# SmartDriveTestStand.net
KiCad netlist of a schematic drawn in EAGLE
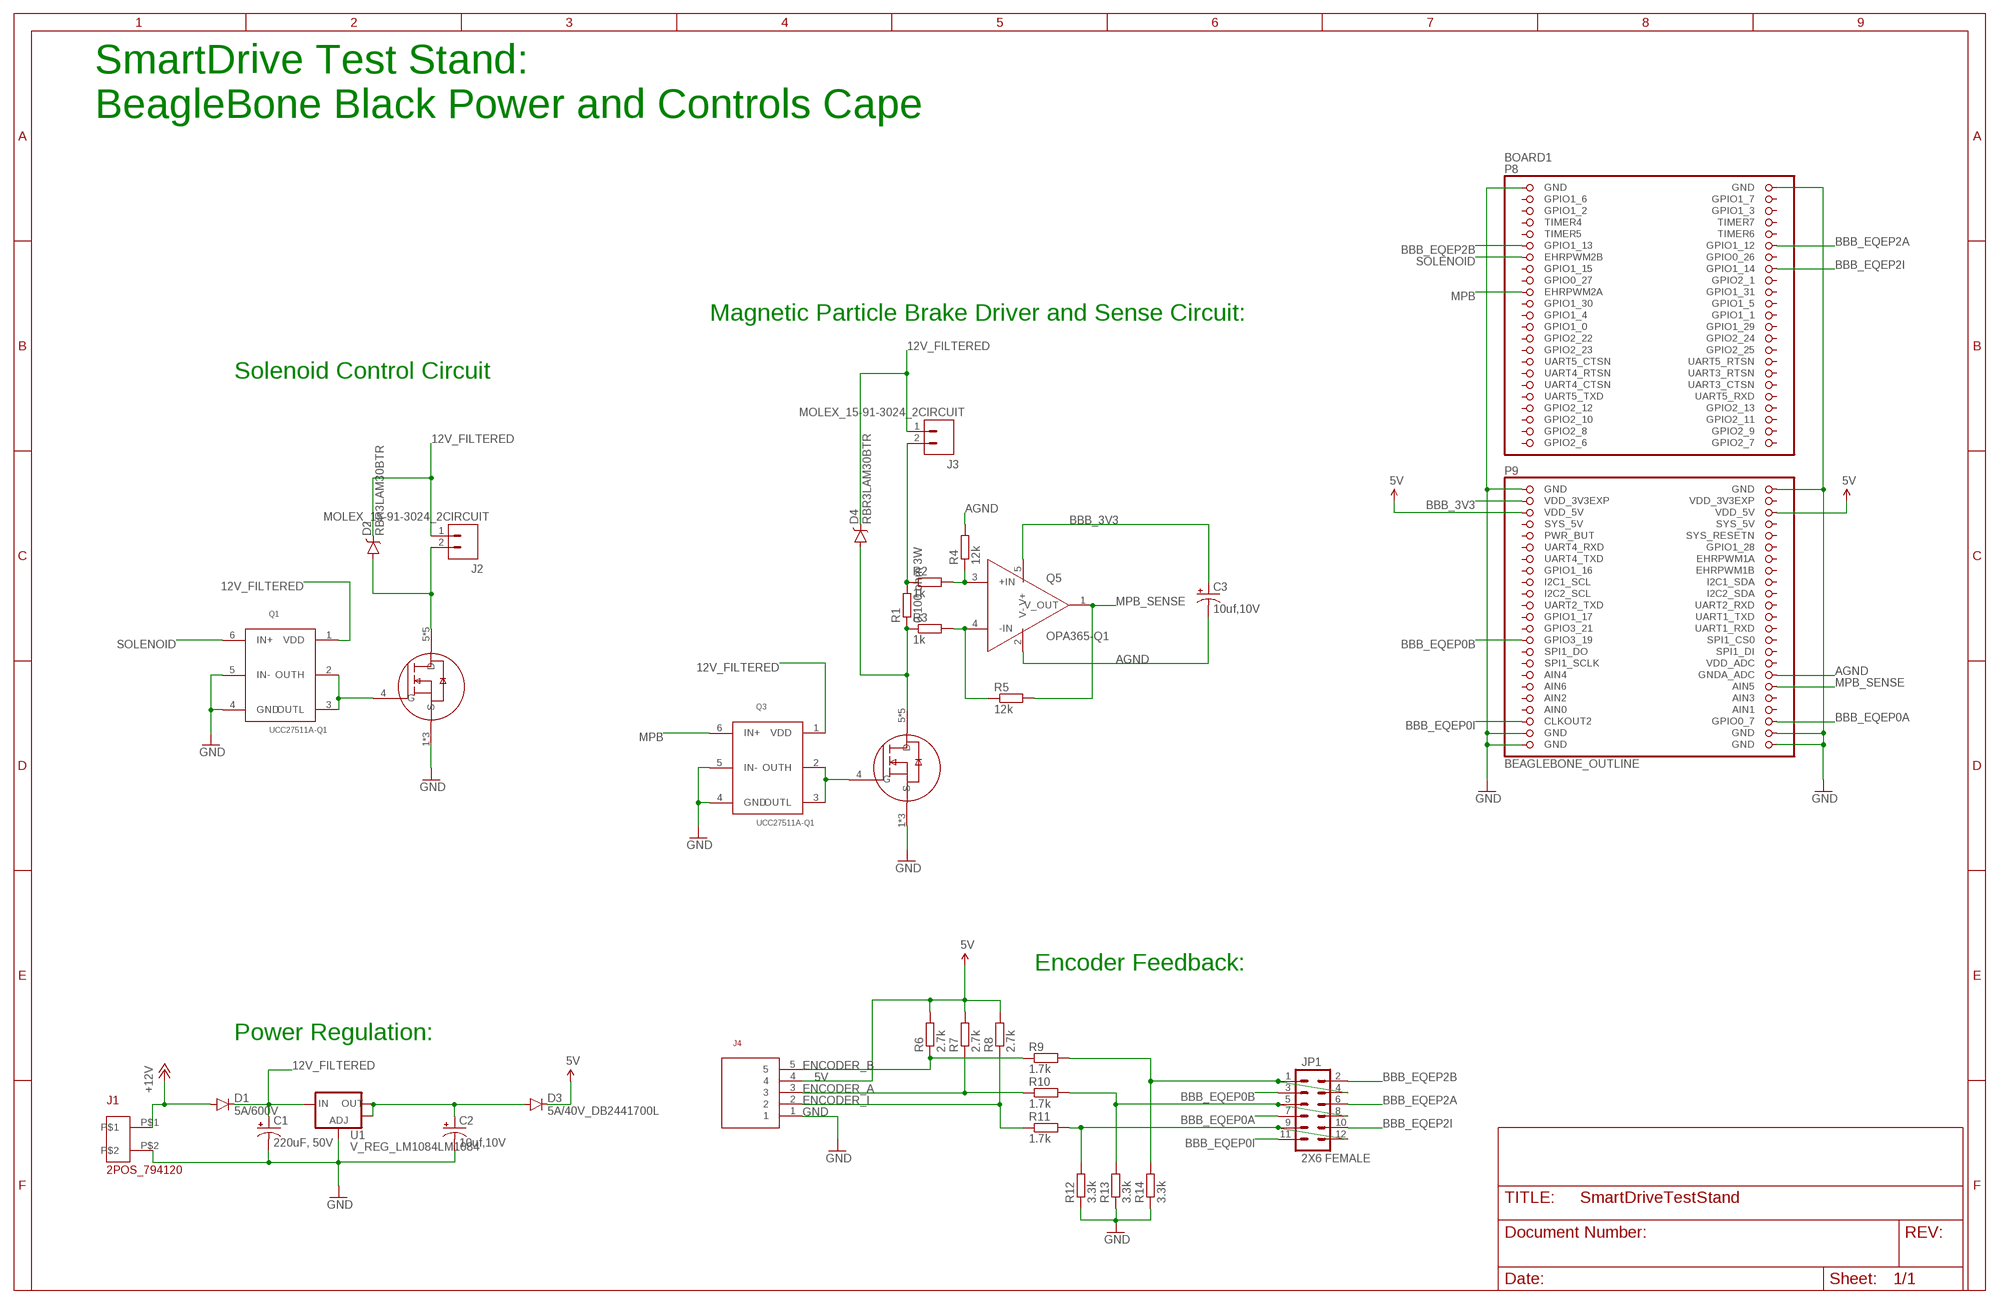
[diagram p0: schematic, sheet 1]

(export (version "E")
  (design (tool "Eeschema 10.0.6"))
  (components
    (comp (ref "BOARD1")
      (value "BEAGLEBONE_OUTLINE")
      (footprint "eagle-import:BEAGLEBONE_SHIELD")
      (libsource (lib "eagle-import") (part "BEAGLEBONE_OUTLINE"))
    )
    (comp (ref "C1")
      (value "220uF, 50V")
      (footprint "eagle-import:PANASONIC_G")
      (libsource (lib "eagle-import") (part "CAP_POLG"))
    )
    (comp (ref "C2")
      (value "10uf,10V")
      (footprint "eagle-import:EIA3216")
      (libsource (lib "eagle-import") (part "SparkFun-Passives_CAP_POL1206"))
    )
    (comp (ref "C3")
      (value "10uf,10V")
      (footprint "eagle-import:EIA3216")
      (libsource (lib "eagle-import") (part "SparkFun-Passives_CAP_POL1206"))
    )
    (comp (ref "D1")
      (value "5A/600V")
      (footprint "eagle-import:SMC")
      (libsource (lib "eagle-import") (part "DIODEES3J"))
    )
    (comp (ref "D2")
      (value "RBR3LAM30BTR")
      (footprint "eagle-import:SMA-DIODE")
      (libsource (lib "eagle-import") (part "DIODE-SCHOTTKYRBR3LAM30B"))
    )
    (comp (ref "D3")
      (value "5A/40V_DB2441700L")
      (footprint "eagle-import:SMA-DIODE_ALT")
      (libsource (lib "eagle-import") (part "DIODESMA-ALT"))
    )
    (comp (ref "D4")
      (value "RBR3LAM30BTR")
      (footprint "eagle-import:SMA-DIODE")
      (libsource (lib "eagle-import") (part "DIODE-SCHOTTKYRBR3LAM30B"))
    )
    (comp (ref "J1")
      (value "2POS_794120")
      (footprint "eagle-import:2POS_794120-1")
      (libsource (lib "eagle-import") (part "2POS_794120"))
    )
    (comp (ref "J2")
      (value "MOLEX_15-91-3024_2CIRCUIT")
      (footprint "eagle-import:MOLEX15-91-3024_2CIRCUIT")
      (libsource (lib "eagle-import") (part "MOLEX_15-91-3024_2CIRCUIT"))
    )
    (comp (ref "J3")
      (value "MOLEX_15-91-3024_2CIRCUIT")
      (footprint "eagle-import:MOLEX15-91-3024_2CIRCUIT")
      (libsource (lib "eagle-import") (part "MOLEX_15-91-3024_2CIRCUIT"))
    )
    (comp (ref "J4")
      (value "MOLEX_15-91-3053_5CIRCUIT")
      (footprint "eagle-import:MOLEX15-91-3053-5CIRCUIT")
      (libsource (lib "eagle-import") (part "MOLEX_15-91-3053_5CIRCUIT"))
    )
    (comp (ref "JP1")
      (value "2X6 FEMALE")
      (footprint "eagle-import:2X6")
      (libsource (lib "eagle-import") (part "M06X2PTH_FEMALE"))
    )
    (comp (ref "Q1")
      (value "UCC27511A-Q1")
      (footprint "eagle-import:SOT23-6")
      (libsource (lib "eagle-import") (part "UCC27511A-Q1"))
    )
    (comp (ref "Q2")
      (value "MOSFET_NCHANNELTI_CSD18533Q5A")
      (footprint "eagle-import:SON_5X6MM_NEXFET")
      (libsource (lib "eagle-import") (part "MOSFET_NCHANNELTI_CSD18533Q5A"))
    )
    (comp (ref "Q3")
      (value "UCC27511A-Q1")
      (footprint "eagle-import:SOT23-6")
      (libsource (lib "eagle-import") (part "UCC27511A-Q1"))
    )
    (comp (ref "Q4")
      (value "MOSFET_NCHANNELTI_CSD18533Q5A")
      (footprint "eagle-import:SON_5X6MM_NEXFET")
      (libsource (lib "eagle-import") (part "MOSFET_NCHANNELTI_CSD18533Q5A"))
    )
    (comp (ref "Q5")
      (value "OPA365-Q1")
      (footprint "eagle-import:SOT23-5")
      (libsource (lib "eagle-import") (part "OPA365-Q1"))
    )
    (comp (ref "R1")
      (value "0.100 ohm 3W")
      (footprint "eagle-import:RESISTOR-2512")
      (libsource (lib "eagle-import") (part "RESISTOR-2512"))
    )
    (comp (ref "R2")
      (value "1k")
      (footprint "eagle-import:RESISTOR-0603")
      (libsource (lib "eagle-import") (part "RESISTOR-0603"))
    )
    (comp (ref "R3")
      (value "1k")
      (footprint "eagle-import:RESISTOR-0603")
      (libsource (lib "eagle-import") (part "RESISTOR-0603"))
    )
    (comp (ref "R4")
      (value "12k")
      (footprint "eagle-import:RESISTOR-0603")
      (libsource (lib "eagle-import") (part "RESISTOR-0603"))
    )
    (comp (ref "R5")
      (value "12k")
      (footprint "eagle-import:RESISTOR-0603")
      (libsource (lib "eagle-import") (part "RESISTOR-0603"))
    )
    (comp (ref "R6")
      (value "2.7k")
      (footprint "eagle-import:RESISTOR-0603")
      (libsource (lib "eagle-import") (part "RESISTOR-0603"))
    )
    (comp (ref "R7")
      (value "2.7k")
      (footprint "eagle-import:RESISTOR-0603")
      (libsource (lib "eagle-import") (part "RESISTOR-0603"))
    )
    (comp (ref "R8")
      (value "2.7k")
      (footprint "eagle-import:RESISTOR-0603")
      (libsource (lib "eagle-import") (part "RESISTOR-0603"))
    )
    (comp (ref "R9")
      (value "1.7k")
      (footprint "eagle-import:RESISTOR-0603")
      (libsource (lib "eagle-import") (part "RESISTOR-0603"))
    )
    (comp (ref "R10")
      (value "1.7k")
      (footprint "eagle-import:RESISTOR-0603")
      (libsource (lib "eagle-import") (part "RESISTOR-0603"))
    )
    (comp (ref "R11")
      (value "1.7k")
      (footprint "eagle-import:RESISTOR-0603")
      (libsource (lib "eagle-import") (part "RESISTOR-0603"))
    )
    (comp (ref "R12")
      (value "3.3k")
      (footprint "eagle-import:RESISTOR-0603")
      (libsource (lib "eagle-import") (part "RESISTOR-0603"))
    )
    (comp (ref "R13")
      (value "3.3k")
      (footprint "eagle-import:RESISTOR-0603")
      (libsource (lib "eagle-import") (part "RESISTOR-0603"))
    )
    (comp (ref "R14")
      (value "3.3k")
      (footprint "eagle-import:RESISTOR-0603")
      (libsource (lib "eagle-import") (part "RESISTOR-0603"))
    )
    (comp (ref "U1")
      (value "V_REG_LM1084LM1084")
      (footprint "eagle-import:TO-263-3")
      (libsource (lib "eagle-import") (part "V_REG_LM1084LM1084"))
    )
  )
  (nets
    (net (code "1") (name "+12V") (class "Default")
      (node (ref "D1") (pin "A") (pinfunction "A_A") (pintype "passive"))
      (node (ref "J1") (pin "P$1") (pinfunction "P$1_P$1") (pintype "bidirectional"))
    )
    (net (code "2") (name "/12V_FILTERED") (class "Default")
      (node (ref "C1") (pin "+") (pinfunction "+_+") (pintype "passive"))
      (node (ref "D1") (pin "C") (pinfunction "C_C") (pintype "passive"))
      (node (ref "D2") (pin "C") (pinfunction "C_C") (pintype "passive"))
      (node (ref "D4") (pin "C") (pinfunction "C_C") (pintype "passive"))
      (node (ref "J2") (pin "1") (pinfunction "1_1") (pintype "passive"))
      (node (ref "J3") (pin "1") (pinfunction "1_1") (pintype "passive"))
      (node (ref "Q1") (pin "1") (pinfunction "VDD_1") (pintype "bidirectional"))
      (node (ref "Q3") (pin "1") (pinfunction "VDD_1") (pintype "bidirectional"))
      (node (ref "U1") (pin "3") (pinfunction "IN_3") (pintype "input"))
    )
    (net (code "3") (name "/AGND") (class "Default")
      (node (ref "BOARD1") (pin "80") (pinfunction "GNDA_ADC_80") (pintype "passive"))
      (node (ref "C3") (pin "C") (pinfunction "-_C") (pintype "passive"))
      (node (ref "Q5") (pin "2") (pinfunction "V-_2") (pintype "power_in"))
      (node (ref "R4") (pin "P$2") (pinfunction "2_P$2") (pintype "passive"))
    )
    (net (code "4") (name "/AIN0") (class "Default")
      (node (ref "BOARD1") (pin "85") (pinfunction "AIN0_85") (pintype "power_in"))
    )
    (net (code "5") (name "/BBB_3V3") (class "Default")
      (node (ref "BOARD1") (pin "49") (pinfunction "VDD_3V3EXP_49") (pintype "power_in"))
      (node (ref "C3") (pin "A") (pinfunction "+_A") (pintype "passive"))
      (node (ref "Q5") (pin "5") (pinfunction "V+_5") (pintype "power_in"))
    )
    (net (code "6") (name "/BBB_EQEP0A") (class "Default")
      (node (ref "BOARD1") (pin "88") (pinfunction "GPIO0_7_88") (pintype "passive"))
      (node (ref "JP1") (pin "7") (pinfunction "7_7") (pintype "passive"))
    )
    (net (code "7") (name "/BBB_EQEP0B") (class "Default")
      (node (ref "BOARD1") (pin "73") (pinfunction "GPIO3_19_73") (pintype "passive"))
      (node (ref "JP1") (pin "3") (pinfunction "3_3") (pintype "passive"))
    )
    (net (code "8") (name "/BBB_EQEP0I") (class "Default")
      (node (ref "BOARD1") (pin "87") (pinfunction "CLKOUT2_87") (pintype "input"))
      (node (ref "JP1") (pin "11") (pinfunction "11_11") (pintype "passive"))
    )
    (net (code "9") (name "/BBB_EQEP2A") (class "Default")
      (node (ref "BOARD1") (pin "12") (pinfunction "GPIO1_12_12") (pintype "passive"))
      (node (ref "JP1") (pin "6") (pinfunction "6_6") (pintype "passive"))
    )
    (net (code "10") (name "/BBB_EQEP2B") (class "Default")
      (node (ref "BOARD1") (pin "11") (pinfunction "GPIO1_13_11") (pintype "passive"))
      (node (ref "JP1") (pin "2") (pinfunction "2_2") (pintype "passive"))
    )
    (net (code "11") (name "/BBB_EQEP2I") (class "Default")
      (node (ref "BOARD1") (pin "16") (pinfunction "GPIO1_14_16") (pintype "passive"))
      (node (ref "JP1") (pin "10") (pinfunction "10_10") (pintype "passive"))
    )
    (net (code "12") (name "/ENCODER_A") (class "Default")
      (node (ref "J4") (pin "3") (pinfunction "3_3") (pintype "passive"))
      (node (ref "R10") (pin "P$1") (pinfunction "1_P$1") (pintype "passive"))
      (node (ref "R7") (pin "P$1") (pinfunction "1_P$1") (pintype "passive"))
    )
    (net (code "13") (name "/ENCODER_B") (class "Default")
      (node (ref "J4") (pin "5") (pinfunction "5_5") (pintype "passive"))
      (node (ref "R6") (pin "P$1") (pinfunction "1_P$1") (pintype "passive"))
      (node (ref "R9") (pin "P$1") (pinfunction "1_P$1") (pintype "passive"))
    )
    (net (code "14") (name "/ENCODER_I") (class "Default")
      (node (ref "J4") (pin "2") (pinfunction "2_2") (pintype "passive"))
      (node (ref "R11") (pin "P$1") (pinfunction "1_P$1") (pintype "passive"))
      (node (ref "R8") (pin "P$1") (pinfunction "1_P$1") (pintype "passive"))
    )
    (net (code "15") (name "/MPB") (class "Default")
      (node (ref "BOARD1") (pin "19") (pinfunction "EHRPWM2A_19") (pintype "passive"))
      (node (ref "Q3") (pin "6") (pinfunction "IN+_6") (pintype "bidirectional"))
    )
    (net (code "16") (name "/MPB_SENSE") (class "Default")
      (node (ref "BOARD1") (pin "82") (pinfunction "AIN5_82") (pintype "passive"))
      (node (ref "Q5") (pin "1") (pinfunction "V_OUT_1") (pintype "output"))
      (node (ref "R5") (pin "P$2") (pinfunction "2_P$2") (pintype "passive"))
    )
    (net (code "17") (name "/SOLENOID") (class "Default")
      (node (ref "BOARD1") (pin "13") (pinfunction "EHRPWM2B_13") (pintype "passive"))
      (node (ref "Q1") (pin "6") (pinfunction "IN+_6") (pintype "bidirectional"))
    )
    (net (code "18") (name "/SYS_5V") (class "Default")
      (node (ref "BOARD1") (pin "53") (pinfunction "SYS_5V_53") (pintype "power_in"))
    )
    (net (code "19") (name "/VDD_3V3EXP") (class "Default")
      (node (ref "BOARD1") (pin "50") (pinfunction "VDD_3V3EXP_50") (pintype "power_in"))
    )
    (net (code "20") (name "5V") (class "Default")
      (node (ref "BOARD1") (pin "51") (pinfunction "VDD_5V_51") (pintype "power_in"))
      (node (ref "BOARD1") (pin "52") (pinfunction "VDD_5V_52") (pintype "power_in"))
      (node (ref "D3") (pin "C") (pinfunction "C_C") (pintype "passive"))
      (node (ref "J4") (pin "4") (pinfunction "4_4") (pintype "passive"))
      (node (ref "R6") (pin "P$2") (pinfunction "2_P$2") (pintype "passive"))
      (node (ref "R7") (pin "P$2") (pinfunction "2_P$2") (pintype "passive"))
      (node (ref "R8") (pin "P$2") (pinfunction "2_P$2") (pintype "passive"))
    )
    (net (code "21") (name "GND") (class "Default")
      (node (ref "BOARD1") (pin "1") (pinfunction "GND_1") (pintype "power_in"))
      (node (ref "BOARD1") (pin "2") (pinfunction "GND_2") (pintype "power_in"))
      (node (ref "BOARD1") (pin "47") (pinfunction "GND_47") (pintype "power_in"))
      (node (ref "BOARD1") (pin "48") (pinfunction "GND_48") (pintype "power_in"))
      (node (ref "BOARD1") (pin "89") (pinfunction "GND_89") (pintype "power_in"))
      (node (ref "BOARD1") (pin "90") (pinfunction "GND_90") (pintype "power_in"))
      (node (ref "BOARD1") (pin "91") (pinfunction "GND_91") (pintype "power_in"))
      (node (ref "BOARD1") (pin "92") (pinfunction "GND_92") (pintype "power_in"))
      (node (ref "C1") (pin "-") (pinfunction "-_-") (pintype "passive"))
      (node (ref "C2") (pin "C") (pinfunction "-_C") (pintype "passive"))
      (node (ref "J1") (pin "P$2") (pinfunction "P$2_P$2") (pintype "bidirectional"))
      (node (ref "J4") (pin "1") (pinfunction "1_1") (pintype "passive"))
      (node (ref "Q1") (pin "4") (pinfunction "GND_4") (pintype "bidirectional"))
      (node (ref "Q1") (pin "5") (pinfunction "IN-_5") (pintype "bidirectional"))
      (node (ref "Q2") (pin "1") (pinfunction "S_1") (pintype "power_in"))
      (node (ref "Q2") (pin "2") (pinfunction "S_2") (pintype "power_in"))
      (node (ref "Q2") (pin "3") (pinfunction "S_3") (pintype "power_in"))
      (node (ref "Q3") (pin "4") (pinfunction "GND_4") (pintype "bidirectional"))
      (node (ref "Q3") (pin "5") (pinfunction "IN-_5") (pintype "bidirectional"))
      (node (ref "Q4") (pin "1") (pinfunction "S_1") (pintype "power_in"))
      (node (ref "Q4") (pin "2") (pinfunction "S_2") (pintype "power_in"))
      (node (ref "Q4") (pin "3") (pinfunction "S_3") (pintype "power_in"))
      (node (ref "R12") (pin "P$1") (pinfunction "1_P$1") (pintype "passive"))
      (node (ref "R13") (pin "P$1") (pinfunction "1_P$1") (pintype "passive"))
      (node (ref "R14") (pin "P$1") (pinfunction "1_P$1") (pintype "passive"))
      (node (ref "U1") (pin "1") (pinfunction "ADJ_1") (pintype "input"))
    )
    (net (code "22") (name "Net-(C2-+)") (class "Default")
      (node (ref "C2") (pin "A") (pinfunction "+_A") (pintype "passive"))
      (node (ref "D3") (pin "A") (pinfunction "A_A") (pintype "passive"))
      (node (ref "U1") (pin "2") (pinfunction "OUT_2") (pintype "output"))
      (node (ref "U1") (pin "4") (pinfunction "OUT_4") (pintype "output"))
    )
    (net (code "23") (name "Net-(D2-PadA)") (class "Default")
      (node (ref "D2") (pin "A") (pinfunction "A_A") (pintype "passive"))
      (node (ref "J2") (pin "2") (pinfunction "2_2") (pintype "passive"))
      (node (ref "Q2") (pin "5") (pinfunction "D_5") (pintype "power_in"))
      (node (ref "Q2") (pin "6") (pinfunction "D_6") (pintype "power_in"))
      (node (ref "Q2") (pin "7") (pinfunction "D_7") (pintype "power_in"))
      (node (ref "Q2") (pin "8") (pinfunction "D_8") (pintype "power_in"))
      (node (ref "Q2") (pin "PAD") (pinfunction "D_PAD") (pintype "power_in"))
    )
    (net (code "24") (name "Net-(Q1-OUTH)") (class "Default")
      (node (ref "Q1") (pin "2") (pinfunction "OUTH_2") (pintype "bidirectional"))
      (node (ref "Q1") (pin "3") (pinfunction "OUTL_3") (pintype "bidirectional"))
      (node (ref "Q2") (pin "4") (pinfunction "G_4") (pintype "input"))
    )
    (net (code "25") (name "Net-(Q3-OUTH)") (class "Default")
      (node (ref "Q3") (pin "2") (pinfunction "OUTH_2") (pintype "bidirectional"))
      (node (ref "Q3") (pin "3") (pinfunction "OUTL_3") (pintype "bidirectional"))
      (node (ref "Q4") (pin "4") (pinfunction "G_4") (pintype "input"))
    )
    (net (code "26") (name "Net-(Q5-+IN)") (class "Default")
      (node (ref "Q5") (pin "3") (pinfunction "+IN_3") (pintype "input"))
      (node (ref "R2") (pin "P$2") (pinfunction "2_P$2") (pintype "passive"))
      (node (ref "R4") (pin "P$1") (pinfunction "1_P$1") (pintype "passive"))
    )
    (net (code "27") (name "Net-(Q5--IN)") (class "Default")
      (node (ref "Q5") (pin "4") (pinfunction "-IN_4") (pintype "input"))
      (node (ref "R3") (pin "P$2") (pinfunction "2_P$2") (pintype "passive"))
      (node (ref "R5") (pin "P$1") (pinfunction "1_P$1") (pintype "passive"))
    )
    (net (code "28") (name "Net-(R2-1)") (class "Default")
      (node (ref "J3") (pin "2") (pinfunction "2_2") (pintype "passive"))
      (node (ref "R1") (pin "2") (pinfunction "2_2") (pintype "passive"))
      (node (ref "R2") (pin "P$1") (pinfunction "1_P$1") (pintype "passive"))
    )
    (net (code "29") (name "Net-(R3-1)") (class "Default")
      (node (ref "D4") (pin "A") (pinfunction "A_A") (pintype "passive"))
      (node (ref "Q4") (pin "5") (pinfunction "D_5") (pintype "power_in"))
      (node (ref "Q4") (pin "6") (pinfunction "D_6") (pintype "power_in"))
      (node (ref "Q4") (pin "7") (pinfunction "D_7") (pintype "power_in"))
      (node (ref "Q4") (pin "8") (pinfunction "D_8") (pintype "power_in"))
      (node (ref "Q4") (pin "PAD") (pinfunction "D_PAD") (pintype "power_in"))
      (node (ref "R1") (pin "1") (pinfunction "1_1") (pintype "passive"))
      (node (ref "R3") (pin "P$1") (pinfunction "1_P$1") (pintype "passive"))
    )
    (net (code "30") (name "Net-(R10-2)") (class "Default")
      (node (ref "JP1") (pin "5") (pinfunction "5_5") (pintype "passive"))
      (node (ref "JP1") (pin "8") (pinfunction "8_8") (pintype "passive"))
      (node (ref "R10") (pin "P$2") (pinfunction "2_P$2") (pintype "passive"))
      (node (ref "R13") (pin "P$2") (pinfunction "2_P$2") (pintype "passive"))
    )
    (net (code "31") (name "Net-(R11-2)") (class "Default")
      (node (ref "JP1") (pin "12") (pinfunction "12_12") (pintype "passive"))
      (node (ref "JP1") (pin "9") (pinfunction "9_9") (pintype "passive"))
      (node (ref "R11") (pin "P$2") (pinfunction "2_P$2") (pintype "passive"))
      (node (ref "R12") (pin "P$2") (pinfunction "2_P$2") (pintype "passive"))
    )
    (net (code "32") (name "Net-(R14-2)") (class "Default")
      (node (ref "JP1") (pin "1") (pinfunction "1_1") (pintype "passive"))
      (node (ref "JP1") (pin "4") (pinfunction "4_4") (pintype "passive"))
      (node (ref "R14") (pin "P$2") (pinfunction "2_P$2") (pintype "passive"))
      (node (ref "R9") (pin "P$2") (pinfunction "2_P$2") (pintype "passive"))
    )
    (net (code "33") (name "unconnected-(BOARD1-AIN1-Pad86)") (class "Default")
      (node (ref "BOARD1") (pin "86") (pinfunction "AIN1_86") (pintype "passive"))
    )
    (net (code "34") (name "unconnected-(BOARD1-AIN2-Pad83)") (class "Default")
      (node (ref "BOARD1") (pin "83") (pinfunction "AIN2_83") (pintype "passive"))
    )
    (net (code "35") (name "unconnected-(BOARD1-AIN3-Pad84)") (class "Default")
      (node (ref "BOARD1") (pin "84") (pinfunction "AIN3_84") (pintype "passive"))
    )
    (net (code "36") (name "unconnected-(BOARD1-AIN4-Pad79)") (class "Default")
      (node (ref "BOARD1") (pin "79") (pinfunction "AIN4_79") (pintype "passive"))
    )
    (net (code "37") (name "unconnected-(BOARD1-AIN6-Pad81)") (class "Default")
      (node (ref "BOARD1") (pin "81") (pinfunction "AIN6_81") (pintype "passive"))
    )
    (net (code "38") (name "unconnected-(BOARD1-EHRPWM1A-Pad60)") (class "Default")
      (node (ref "BOARD1") (pin "60") (pinfunction "EHRPWM1A_60") (pintype "passive"))
    )
    (net (code "39") (name "unconnected-(BOARD1-EHRPWM1B-Pad62)") (class "Default")
      (node (ref "BOARD1") (pin "62") (pinfunction "EHRPWM1B_62") (pintype "passive"))
    )
    (net (code "40") (name "unconnected-(BOARD1-GPIO0_26-Pad14)") (class "Default")
      (node (ref "BOARD1") (pin "14") (pinfunction "GPIO0_26_14") (pintype "passive"))
    )
    (net (code "41") (name "unconnected-(BOARD1-GPIO0_27-Pad17)") (class "Default")
      (node (ref "BOARD1") (pin "17") (pinfunction "GPIO0_27_17") (pintype "passive"))
    )
    (net (code "42") (name "unconnected-(BOARD1-GPIO1_0-Pad25)") (class "Default")
      (node (ref "BOARD1") (pin "25") (pinfunction "GPIO1_0_25") (pintype "passive"))
    )
    (net (code "43") (name "unconnected-(BOARD1-GPIO1_1-Pad24)") (class "Default")
      (node (ref "BOARD1") (pin "24") (pinfunction "GPIO1_1_24") (pintype "passive"))
    )
    (net (code "44") (name "unconnected-(BOARD1-GPIO1_2-Pad5)") (class "Default")
      (node (ref "BOARD1") (pin "5") (pinfunction "GPIO1_2_5") (pintype "passive"))
    )
    (net (code "45") (name "unconnected-(BOARD1-GPIO1_3-Pad6)") (class "Default")
      (node (ref "BOARD1") (pin "6") (pinfunction "GPIO1_3_6") (pintype "passive"))
    )
    (net (code "46") (name "unconnected-(BOARD1-GPIO1_4-Pad23)") (class "Default")
      (node (ref "BOARD1") (pin "23") (pinfunction "GPIO1_4_23") (pintype "passive"))
    )
    (net (code "47") (name "unconnected-(BOARD1-GPIO1_5-Pad22)") (class "Default")
      (node (ref "BOARD1") (pin "22") (pinfunction "GPIO1_5_22") (pintype "passive"))
    )
    (net (code "48") (name "unconnected-(BOARD1-GPIO1_6-Pad3)") (class "Default")
      (node (ref "BOARD1") (pin "3") (pinfunction "GPIO1_6_3") (pintype "passive"))
    )
    (net (code "49") (name "unconnected-(BOARD1-GPIO1_7-Pad4)") (class "Default")
      (node (ref "BOARD1") (pin "4") (pinfunction "GPIO1_7_4") (pintype "passive"))
    )
    (net (code "50") (name "unconnected-(BOARD1-GPIO1_15-Pad15)") (class "Default")
      (node (ref "BOARD1") (pin "15") (pinfunction "GPIO1_15_15") (pintype "passive"))
    )
    (net (code "51") (name "unconnected-(BOARD1-GPIO1_16-Pad61)") (class "Default")
      (node (ref "BOARD1") (pin "61") (pinfunction "GPIO1_16_61") (pintype "passive"))
    )
    (net (code "52") (name "unconnected-(BOARD1-GPIO1_17-Pad69)") (class "Default")
      (node (ref "BOARD1") (pin "69") (pinfunction "GPIO1_17_69") (pintype "passive"))
    )
    (net (code "53") (name "unconnected-(BOARD1-GPIO1_28-Pad58)") (class "Default")
      (node (ref "BOARD1") (pin "58") (pinfunction "GPIO1_28_58") (pintype "passive"))
    )
    (net (code "54") (name "unconnected-(BOARD1-GPIO1_29-Pad26)") (class "Default")
      (node (ref "BOARD1") (pin "26") (pinfunction "GPIO1_29_26") (pintype "passive"))
    )
    (net (code "55") (name "unconnected-(BOARD1-GPIO1_30-Pad21)") (class "Default")
      (node (ref "BOARD1") (pin "21") (pinfunction "GPIO1_30_21") (pintype "passive"))
    )
    (net (code "56") (name "unconnected-(BOARD1-GPIO1_31-Pad20)") (class "Default")
      (node (ref "BOARD1") (pin "20") (pinfunction "GPIO1_31_20") (pintype "passive"))
    )
    (net (code "57") (name "unconnected-(BOARD1-GPIO2_1-Pad18)") (class "Default")
      (node (ref "BOARD1") (pin "18") (pinfunction "GPIO2_1_18") (pintype "passive"))
    )
    (net (code "58") (name "unconnected-(BOARD1-GPIO2_6-Pad45)") (class "Default")
      (node (ref "BOARD1") (pin "45") (pinfunction "GPIO2_6_45") (pintype "passive"))
    )
    (net (code "59") (name "unconnected-(BOARD1-GPIO2_7-Pad46)") (class "Default")
      (node (ref "BOARD1") (pin "46") (pinfunction "GPIO2_7_46") (pintype "passive"))
    )
    (net (code "60") (name "unconnected-(BOARD1-GPIO2_8-Pad43)") (class "Default")
      (node (ref "BOARD1") (pin "43") (pinfunction "GPIO2_8_43") (pintype "passive"))
    )
    (net (code "61") (name "unconnected-(BOARD1-GPIO2_9-Pad44)") (class "Default")
      (node (ref "BOARD1") (pin "44") (pinfunction "GPIO2_9_44") (pintype "passive"))
    )
    (net (code "62") (name "unconnected-(BOARD1-GPIO2_10-Pad41)") (class "Default")
      (node (ref "BOARD1") (pin "41") (pinfunction "GPIO2_10_41") (pintype "passive"))
    )
    (net (code "63") (name "unconnected-(BOARD1-GPIO2_11-Pad42)") (class "Default")
      (node (ref "BOARD1") (pin "42") (pinfunction "GPIO2_11_42") (pintype "passive"))
    )
    (net (code "64") (name "unconnected-(BOARD1-GPIO2_12-Pad39)") (class "Default")
      (node (ref "BOARD1") (pin "39") (pinfunction "GPIO2_12_39") (pintype "passive"))
    )
    (net (code "65") (name "unconnected-(BOARD1-GPIO2_13-Pad40)") (class "Default")
      (node (ref "BOARD1") (pin "40") (pinfunction "GPIO2_13_40") (pintype "passive"))
    )
    (net (code "66") (name "unconnected-(BOARD1-GPIO2_22-Pad27)") (class "Default")
      (node (ref "BOARD1") (pin "27") (pinfunction "GPIO2_22_27") (pintype "passive"))
    )
    (net (code "67") (name "unconnected-(BOARD1-GPIO2_23-Pad29)") (class "Default")
      (node (ref "BOARD1") (pin "29") (pinfunction "GPIO2_23_29") (pintype "passive"))
    )
    (net (code "68") (name "unconnected-(BOARD1-GPIO2_24-Pad28)") (class "Default")
      (node (ref "BOARD1") (pin "28") (pinfunction "GPIO2_24_28") (pintype "passive"))
    )
    (net (code "69") (name "unconnected-(BOARD1-GPIO2_25-Pad30)") (class "Default")
      (node (ref "BOARD1") (pin "30") (pinfunction "GPIO2_25_30") (pintype "passive"))
    )
    (net (code "70") (name "unconnected-(BOARD1-GPIO3_21-Pad71)") (class "Default")
      (node (ref "BOARD1") (pin "71") (pinfunction "GPIO3_21_71") (pintype "passive"))
    )
    (net (code "71") (name "unconnected-(BOARD1-I2C1_SCL-Pad63)") (class "Default")
      (node (ref "BOARD1") (pin "63") (pinfunction "I2C1_SCL_63") (pintype "passive"))
    )
    (net (code "72") (name "unconnected-(BOARD1-I2C1_SDA-Pad64)") (class "Default")
      (node (ref "BOARD1") (pin "64") (pinfunction "I2C1_SDA_64") (pintype "passive"))
    )
    (net (code "73") (name "unconnected-(BOARD1-I2C2_SCL-Pad65)") (class "Default")
      (node (ref "BOARD1") (pin "65") (pinfunction "I2C2_SCL_65") (pintype "passive"))
    )
    (net (code "74") (name "unconnected-(BOARD1-I2C2_SDA-Pad66)") (class "Default")
      (node (ref "BOARD1") (pin "66") (pinfunction "I2C2_SDA_66") (pintype "passive"))
    )
    (net (code "75") (name "unconnected-(BOARD1-PWR_BUT-Pad55)") (class "Default")
      (node (ref "BOARD1") (pin "55") (pinfunction "PWR_BUT_55") (pintype "passive"))
    )
    (net (code "76") (name "unconnected-(BOARD1-SPI1_CS0-Pad74)") (class "Default")
      (node (ref "BOARD1") (pin "74") (pinfunction "SPI1_CS0_74") (pintype "passive"))
    )
    (net (code "77") (name "unconnected-(BOARD1-SPI1_DI-Pad76)") (class "Default")
      (node (ref "BOARD1") (pin "76") (pinfunction "SPI1_DI_76") (pintype "passive"))
    )
    (net (code "78") (name "unconnected-(BOARD1-SPI1_DO-Pad75)") (class "Default")
      (node (ref "BOARD1") (pin "75") (pinfunction "SPI1_DO_75") (pintype "passive"))
    )
    (net (code "79") (name "unconnected-(BOARD1-SPI1_SCLK-Pad77)") (class "Default")
      (node (ref "BOARD1") (pin "77") (pinfunction "SPI1_SCLK_77") (pintype "passive"))
    )
    (net (code "80") (name "unconnected-(BOARD1-SYS_5V-Pad54)") (class "Default")
      (node (ref "BOARD1") (pin "54") (pinfunction "SYS_5V_54") (pintype "passive"))
    )
    (net (code "81") (name "unconnected-(BOARD1-SYS_RESETN-Pad56)") (class "Default")
      (node (ref "BOARD1") (pin "56") (pinfunction "SYS_RESETN_56") (pintype "passive"))
    )
    (net (code "82") (name "unconnected-(BOARD1-TIMER4-Pad7)") (class "Default")
      (node (ref "BOARD1") (pin "7") (pinfunction "TIMER4_7") (pintype "passive"))
    )
    (net (code "83") (name "unconnected-(BOARD1-TIMER5-Pad9)") (class "Default")
      (node (ref "BOARD1") (pin "9") (pinfunction "TIMER5_9") (pintype "passive"))
    )
    (net (code "84") (name "unconnected-(BOARD1-TIMER6-Pad10)") (class "Default")
      (node (ref "BOARD1") (pin "10") (pinfunction "TIMER6_10") (pintype "passive"))
    )
    (net (code "85") (name "unconnected-(BOARD1-TIMER7-Pad8)") (class "Default")
      (node (ref "BOARD1") (pin "8") (pinfunction "TIMER7_8") (pintype "passive"))
    )
    (net (code "86") (name "unconnected-(BOARD1-UART1_RXD-Pad72)") (class "Default")
      (node (ref "BOARD1") (pin "72") (pinfunction "UART1_RXD_72") (pintype "passive"))
    )
    (net (code "87") (name "unconnected-(BOARD1-UART1_TXD-Pad70)") (class "Default")
      (node (ref "BOARD1") (pin "70") (pinfunction "UART1_TXD_70") (pintype "passive"))
    )
    (net (code "88") (name "unconnected-(BOARD1-UART2_RXD-Pad68)") (class "Default")
      (node (ref "BOARD1") (pin "68") (pinfunction "UART2_RXD_68") (pintype "passive"))
    )
    (net (code "89") (name "unconnected-(BOARD1-UART2_TXD-Pad67)") (class "Default")
      (node (ref "BOARD1") (pin "67") (pinfunction "UART2_TXD_67") (pintype "passive"))
    )
    (net (code "90") (name "unconnected-(BOARD1-UART3_CTSN-Pad36)") (class "Default")
      (node (ref "BOARD1") (pin "36") (pinfunction "UART3_CTSN_36") (pintype "passive"))
    )
    (net (code "91") (name "unconnected-(BOARD1-UART3_RTSN-Pad34)") (class "Default")
      (node (ref "BOARD1") (pin "34") (pinfunction "UART3_RTSN_34") (pintype "passive"))
    )
    (net (code "92") (name "unconnected-(BOARD1-UART4_CTSN-Pad35)") (class "Default")
      (node (ref "BOARD1") (pin "35") (pinfunction "UART4_CTSN_35") (pintype "passive"))
    )
    (net (code "93") (name "unconnected-(BOARD1-UART4_RTSN-Pad33)") (class "Default")
      (node (ref "BOARD1") (pin "33") (pinfunction "UART4_RTSN_33") (pintype "passive"))
    )
    (net (code "94") (name "unconnected-(BOARD1-UART4_RXD-Pad57)") (class "Default")
      (node (ref "BOARD1") (pin "57") (pinfunction "UART4_RXD_57") (pintype "passive"))
    )
    (net (code "95") (name "unconnected-(BOARD1-UART4_TXD-Pad59)") (class "Default")
      (node (ref "BOARD1") (pin "59") (pinfunction "UART4_TXD_59") (pintype "passive"))
    )
    (net (code "96") (name "unconnected-(BOARD1-UART5_CTSN-Pad31)") (class "Default")
      (node (ref "BOARD1") (pin "31") (pinfunction "UART5_CTSN_31") (pintype "passive"))
    )
    (net (code "97") (name "unconnected-(BOARD1-UART5_RTSN-Pad32)") (class "Default")
      (node (ref "BOARD1") (pin "32") (pinfunction "UART5_RTSN_32") (pintype "passive"))
    )
    (net (code "98") (name "unconnected-(BOARD1-UART5_RXD-Pad38)") (class "Default")
      (node (ref "BOARD1") (pin "38") (pinfunction "UART5_RXD_38") (pintype "passive"))
    )
    (net (code "99") (name "unconnected-(BOARD1-UART5_TXD-Pad37)") (class "Default")
      (node (ref "BOARD1") (pin "37") (pinfunction "UART5_TXD_37") (pintype "passive"))
    )
    (net (code "100") (name "unconnected-(BOARD1-VDD_ADC-Pad78)") (class "Default")
      (node (ref "BOARD1") (pin "78") (pinfunction "VDD_ADC_78") (pintype "passive"))
    )
  )
)
